# adau1772-1372-boosterpack.net
KiCad netlist of a schematic drawn in EAGLE
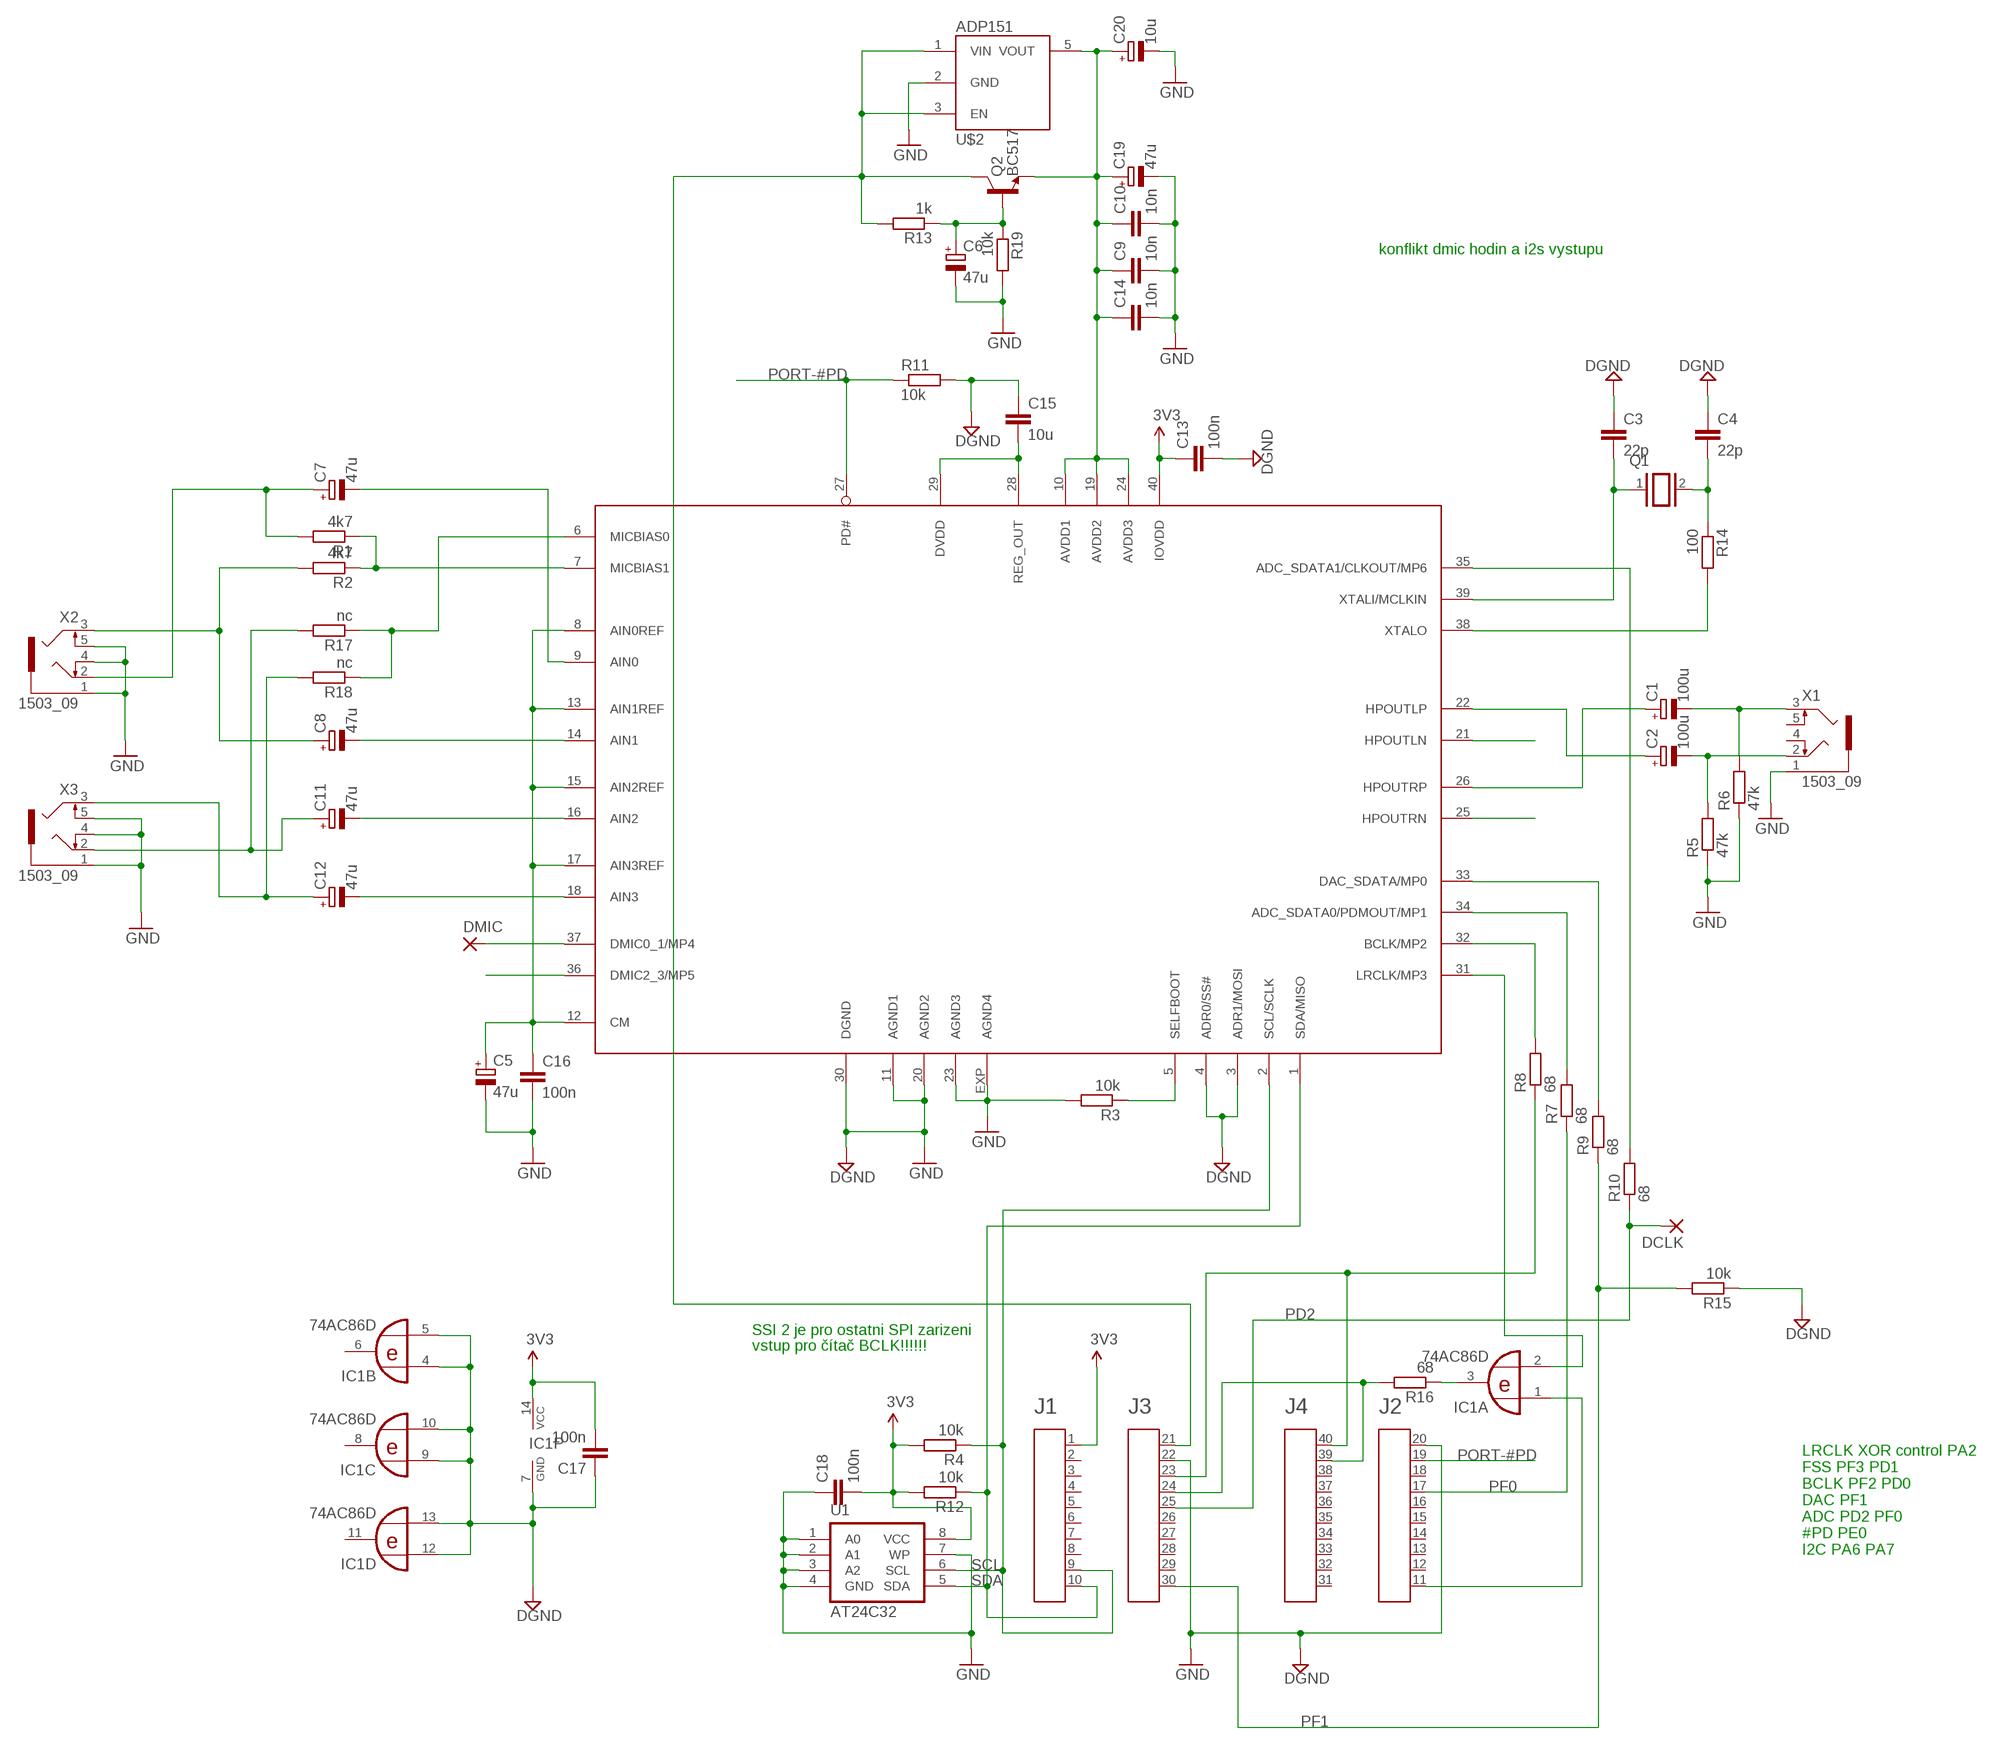
[diagram p0: schematic, sheet 1]

(export (version "E")
  (design (tool "Eeschema 10.0.6"))
  (components
    (comp (ref "A1")
      (value "HEADER4X10-BOOSTERPACK")
      (footprint "eagle-import:4X10-BOOSTERPACK")
      (libsource (lib "eagle-import") (part "HEADER4X10-BOOSTERPACK"))
    )
    (comp (ref "C1")
      (value "100u")
      (footprint "eagle-import:E2,5-7")
      (libsource (lib "eagle-import") (part "CPOL-EUE2.5-7"))
    )
    (comp (ref "C2")
      (value "100u")
      (footprint "eagle-import:E2,5-7")
      (libsource (lib "eagle-import") (part "CPOL-EUE2.5-7"))
    )
    (comp (ref "C3")
      (value "22p")
      (footprint "eagle-import:C0805K")
      (libsource (lib "eagle-import") (part "C-EUC0805K"))
    )
    (comp (ref "C4")
      (value "22p")
      (footprint "eagle-import:C0805K")
      (libsource (lib "eagle-import") (part "C-EUC0805K"))
    )
    (comp (ref "C5")
      (value "47u")
      (footprint "eagle-import:SMC_C")
      (libsource (lib "eagle-import") (part "CPOL-EUSMCC"))
    )
    (comp (ref "C6")
      (value "47u")
      (footprint "eagle-import:E2-5")
      (libsource (lib "eagle-import") (part "CPOL-EUE2-5"))
    )
    (comp (ref "C7")
      (value "47u")
      (footprint "eagle-import:E2-5")
      (libsource (lib "eagle-import") (part "CPOL-EUE2-5"))
    )
    (comp (ref "C8")
      (value "47u")
      (footprint "eagle-import:E2-5")
      (libsource (lib "eagle-import") (part "CPOL-EUE2-5"))
    )
    (comp (ref "C9")
      (value "10n")
      (footprint "eagle-import:C0805")
      (libsource (lib "eagle-import") (part "C-EUC0805"))
    )
    (comp (ref "C10")
      (value "10n")
      (footprint "eagle-import:C0805")
      (libsource (lib "eagle-import") (part "C-EUC0805"))
    )
    (comp (ref "C11")
      (value "47u")
      (footprint "eagle-import:E2-5")
      (libsource (lib "eagle-import") (part "CPOL-EUE2-5"))
    )
    (comp (ref "C12")
      (value "47u")
      (footprint "eagle-import:E2-5")
      (libsource (lib "eagle-import") (part "CPOL-EUE2-5"))
    )
    (comp (ref "C13")
      (value "100n")
      (footprint "eagle-import:C0805")
      (libsource (lib "eagle-import") (part "C-EUC0805"))
    )
    (comp (ref "C14")
      (value "10n")
      (footprint "eagle-import:C0805")
      (libsource (lib "eagle-import") (part "C-EUC0805"))
    )
    (comp (ref "C15")
      (value "10u")
      (footprint "eagle-import:C0805")
      (libsource (lib "eagle-import") (part "C-EUC0805"))
    )
    (comp (ref "C16")
      (value "100n")
      (footprint "eagle-import:C0805")
      (libsource (lib "eagle-import") (part "C-EUC0805"))
    )
    (comp (ref "C17")
      (value "100n")
      (footprint "eagle-import:C0805")
      (libsource (lib "eagle-import") (part "C-EUC0805"))
    )
    (comp (ref "C18")
      (value "100n")
      (footprint "eagle-import:C0805")
      (libsource (lib "eagle-import") (part "C-EUC0805"))
    )
    (comp (ref "C19")
      (value "47u")
      (footprint "eagle-import:E2-5")
      (libsource (lib "eagle-import") (part "CPOL-EUE2-5"))
    )
    (comp (ref "C20")
      (value "10u")
      (footprint "eagle-import:SMC_A")
      (libsource (lib "eagle-import") (part "CPOL-EUSMCA"))
    )
    (comp (ref "DCLK")
      (value "SMD2")
      (footprint "eagle-import:SMD1,27-2,54")
      (libsource (lib "eagle-import") (part "SMD2"))
    )
    (comp (ref "DMIC")
      (value "SMD2")
      (footprint "eagle-import:SMD1,27-2,54")
      (libsource (lib "eagle-import") (part "SMD2"))
    )
    (comp (ref "IC1")
      (value "74AC86D")
      (footprint "eagle-import:SO14")
      (libsource (lib "eagle-import") (part "7486DAC"))
    )
    (comp (ref "Q1")
      (value "XTAL/S")
      (footprint "eagle-import:QS")
      (libsource (lib "eagle-import") (part "XTAL/S"))
    )
    (comp (ref "Q2")
      (value "BC517")
      (footprint "eagle-import:TO92-")
      (libsource (lib "eagle-import") (part "BC550"))
    )
    (comp (ref "R1")
      (value "4k7")
      (footprint "eagle-import:R1206")
      (libsource (lib "eagle-import") (part "R-EU_R1206"))
    )
    (comp (ref "R2")
      (value "4k7")
      (footprint "eagle-import:R1206")
      (libsource (lib "eagle-import") (part "R-EU_R1206"))
    )
    (comp (ref "R3")
      (value "10k")
      (footprint "eagle-import:R1206")
      (libsource (lib "eagle-import") (part "R-EU_R1206"))
    )
    (comp (ref "R4")
      (value "10k")
      (footprint "eagle-import:R0805")
      (libsource (lib "eagle-import") (part "R-EU_R0805"))
    )
    (comp (ref "R5")
      (value "47k")
      (footprint "eagle-import:R0805")
      (libsource (lib "eagle-import") (part "R-EU_R0805"))
    )
    (comp (ref "R6")
      (value "47k")
      (footprint "eagle-import:R0805")
      (libsource (lib "eagle-import") (part "R-EU_R0805"))
    )
    (comp (ref "R7")
      (value "68")
      (footprint "eagle-import:R1206")
      (libsource (lib "eagle-import") (part "R-EU_R1206"))
    )
    (comp (ref "R8")
      (value "68")
      (footprint "eagle-import:R1206")
      (libsource (lib "eagle-import") (part "R-EU_R1206"))
    )
    (comp (ref "R9")
      (value "68")
      (footprint "eagle-import:R1206")
      (libsource (lib "eagle-import") (part "R-EU_R1206"))
    )
    (comp (ref "R10")
      (value "68")
      (footprint "eagle-import:R1206")
      (libsource (lib "eagle-import") (part "R-EU_R1206"))
    )
    (comp (ref "R11")
      (value "10k")
      (footprint "eagle-import:R0805")
      (libsource (lib "eagle-import") (part "R-EU_R0805"))
    )
    (comp (ref "R12")
      (value "10k")
      (footprint "eagle-import:R0805")
      (libsource (lib "eagle-import") (part "R-EU_R0805"))
    )
    (comp (ref "R13")
      (value "1k")
      (footprint "eagle-import:R0805")
      (libsource (lib "eagle-import") (part "R-EU_R0805"))
    )
    (comp (ref "R14")
      (value "100")
      (footprint "eagle-import:R0805")
      (libsource (lib "eagle-import") (part "R-EU_R0805"))
    )
    (comp (ref "R15")
      (value "10k")
      (footprint "eagle-import:R1206")
      (libsource (lib "eagle-import") (part "R-EU_R1206"))
    )
    (comp (ref "R16")
      (value "68")
      (footprint "eagle-import:R1206")
      (libsource (lib "eagle-import") (part "R-EU_R1206"))
    )
    (comp (ref "R17")
      (value "nc")
      (footprint "eagle-import:R1206")
      (libsource (lib "eagle-import") (part "R-EU_R1206"))
    )
    (comp (ref "R18")
      (value "nc")
      (footprint "eagle-import:R1206")
      (libsource (lib "eagle-import") (part "R-EU_R1206"))
    )
    (comp (ref "R19")
      (value "10k")
      (footprint "eagle-import:R0805")
      (libsource (lib "eagle-import") (part "R-EU_R0805"))
    )
    (comp (ref "U$1")
      (value "ADAU1772")
      (footprint "eagle-import:LFPSC-40")
      (libsource (lib "eagle-import") (part "ADAU1772"))
    )
    (comp (ref "U$2")
      (value "ADP151")
      (footprint "eagle-import:SOT23-5")
      (libsource (lib "eagle-import") (part "ADP151"))
    )
    (comp (ref "U1")
      (value "AT24C32")
      (footprint "eagle-import:SO08-8S1")
      (libsource (lib "eagle-import") (part "AT24CXX"))
    )
    (comp (ref "X1")
      (value "1503_09")
      (footprint "eagle-import:1503_09")
      (libsource (lib "eagle-import") (part "1503_09"))
    )
    (comp (ref "X2")
      (value "1503_09")
      (footprint "eagle-import:1503_09")
      (fields (field (name "OC_FARNELL") "1243244") (field (name "OC_NEWARK") "unknown"))
      (libsource (lib "eagle-import") (part "1503_09"))
    )
    (comp (ref "X3")
      (value "1503_09")
      (footprint "eagle-import:1503_09")
      (fields (field (name "OC_FARNELL") "1243244") (field (name "OC_NEWARK") "unknown"))
      (libsource (lib "eagle-import") (part "1503_09"))
    )
  )
  (nets
    (net (code "1") (name "/PD2") (class "Default")
      (node (ref "A1") (pin "25") (pinfunction "P$25_25") (pintype "bidirectional"))
      (node (ref "DCLK") (pin "1") (pinfunction "P_1") (pintype "passive"))
      (node (ref "R10") (pin "1") (pinfunction "1_1") (pintype "passive"))
    )
    (net (code "2") (name "/PF0") (class "Default")
      (node (ref "A1") (pin "17") (pinfunction "P$17_17") (pintype "bidirectional"))
      (node (ref "R7") (pin "1") (pinfunction "1_1") (pintype "passive"))
    )
    (net (code "3") (name "/PF1") (class "Default")
      (node (ref "A1") (pin "30") (pinfunction "P$30_30") (pintype "bidirectional"))
      (node (ref "R15") (pin "2") (pinfunction "2_2") (pintype "passive"))
      (node (ref "R9") (pin "1") (pinfunction "1_1") (pintype "passive"))
    )
    (net (code "4") (name "/PORT-#PD") (class "Default")
      (node (ref "A1") (pin "19") (pinfunction "P$19_19") (pintype "bidirectional"))
      (node (ref "R11") (pin "1") (pinfunction "1_1") (pintype "passive"))
      (node (ref "U$1") (pin "27") (pinfunction "PD#_27") (pintype "bidirectional"))
    )
    (net (code "5") (name "/SCL") (class "Default")
      (node (ref "A1") (pin "9") (pinfunction "P$9_9") (pintype "bidirectional"))
      (node (ref "R4") (pin "1") (pinfunction "1_1") (pintype "passive"))
      (node (ref "U$1") (pin "2") (pinfunction "SCL/SCLK_2") (pintype "bidirectional"))
      (node (ref "U1") (pin "6") (pinfunction "SCL_6") (pintype "bidirectional"))
    )
    (net (code "6") (name "/SDA") (class "Default")
      (node (ref "A1") (pin "10") (pinfunction "P$10_10") (pintype "bidirectional"))
      (node (ref "R12") (pin "1") (pinfunction "1_1") (pintype "passive"))
      (node (ref "U$1") (pin "1") (pinfunction "SDA/MISO_1") (pintype "bidirectional"))
      (node (ref "U1") (pin "5") (pinfunction "SDA_5") (pintype "bidirectional"))
    )
    (net (code "7") (name "3V3") (class "Default")
      (node (ref "A1") (pin "1") (pinfunction "P$1_1") (pintype "bidirectional"))
      (node (ref "C13") (pin "1") (pinfunction "1_1") (pintype "passive"))
      (node (ref "C17") (pin "2") (pinfunction "2_2") (pintype "passive"))
      (node (ref "C18") (pin "2") (pinfunction "2_2") (pintype "passive"))
      (node (ref "IC1") (pin "14") (pinfunction "VCC_14") (pintype "power_in"))
      (node (ref "R12") (pin "2") (pinfunction "2_2") (pintype "passive"))
      (node (ref "R4") (pin "2") (pinfunction "2_2") (pintype "passive"))
      (node (ref "U$1") (pin "40") (pinfunction "IOVDD_40") (pintype "bidirectional"))
      (node (ref "U1") (pin "8") (pinfunction "VCC_8") (pintype "power_in"))
    )
    (net (code "8") (name "DGND") (class "Default")
      (node (ref "A1") (pin "20") (pinfunction "P$20_20") (pintype "bidirectional"))
      (node (ref "A1") (pin "22") (pinfunction "P$22_22") (pintype "bidirectional"))
      (node (ref "C10") (pin "2") (pinfunction "2_2") (pintype "passive"))
      (node (ref "C13") (pin "2") (pinfunction "2_2") (pintype "passive"))
      (node (ref "C14") (pin "2") (pinfunction "2_2") (pintype "passive"))
      (node (ref "C15") (pin "1") (pinfunction "1_1") (pintype "passive"))
      (node (ref "C16") (pin "2") (pinfunction "2_2") (pintype "passive"))
      (node (ref "C17") (pin "1") (pinfunction "1_1") (pintype "passive"))
      (node (ref "C18") (pin "1") (pinfunction "1_1") (pintype "passive"))
      (node (ref "C19") (pin "-") (pinfunction "-_-") (pintype "passive"))
      (node (ref "C20") (pin "-") (pinfunction "-_-") (pintype "passive"))
      (node (ref "C3") (pin "1") (pinfunction "1_1") (pintype "passive"))
      (node (ref "C4") (pin "1") (pinfunction "1_1") (pintype "passive"))
      (node (ref "C5") (pin "-") (pinfunction "-_-") (pintype "passive"))
      (node (ref "C6") (pin "-") (pinfunction "-_-") (pintype "passive"))
      (node (ref "C9") (pin "2") (pinfunction "2_2") (pintype "passive"))
      (node (ref "IC1") (pin "10") (pinfunction "I1_10") (pintype "input"))
      (node (ref "IC1") (pin "12") (pinfunction "I0_12") (pintype "input"))
      (node (ref "IC1") (pin "13") (pinfunction "I1_13") (pintype "input"))
      (node (ref "IC1") (pin "4") (pinfunction "I0_4") (pintype "input"))
      (node (ref "IC1") (pin "5") (pinfunction "I1_5") (pintype "input"))
      (node (ref "IC1") (pin "7") (pinfunction "GND_7") (pintype "power_in"))
      (node (ref "IC1") (pin "9") (pinfunction "I0_9") (pintype "input"))
      (node (ref "R11") (pin "2") (pinfunction "2_2") (pintype "passive"))
      (node (ref "R15") (pin "1") (pinfunction "1_1") (pintype "passive"))
      (node (ref "R19") (pin "2") (pinfunction "2_2") (pintype "passive"))
      (node (ref "R3") (pin "2") (pinfunction "2_2") (pintype "passive"))
      (node (ref "R5") (pin "1") (pinfunction "1_1") (pintype "passive"))
      (node (ref "R6") (pin "1") (pinfunction "1_1") (pintype "passive"))
      (node (ref "U$1") (pin "11") (pinfunction "AGND1_11") (pintype "bidirectional"))
      (node (ref "U$1") (pin "20") (pinfunction "AGND2_20") (pintype "bidirectional"))
      (node (ref "U$1") (pin "23") (pinfunction "AGND3_23") (pintype "bidirectional"))
      (node (ref "U$1") (pin "3") (pinfunction "ADR1/MOSI_3") (pintype "bidirectional"))
      (node (ref "U$1") (pin "30") (pinfunction "DGND_30") (pintype "bidirectional"))
      (node (ref "U$1") (pin "4") (pinfunction "ADR0/SS#_4") (pintype "bidirectional"))
      (node (ref "U$1") (pin "EXP") (pinfunction "AGND4_EXP") (pintype "bidirectional"))
      (node (ref "U$2") (pin "2") (pinfunction "GND_2") (pintype "bidirectional"))
      (node (ref "U1") (pin "1") (pinfunction "A0_1") (pintype "input"))
      (node (ref "U1") (pin "2") (pinfunction "A1_2") (pintype "input"))
      (node (ref "U1") (pin "3") (pinfunction "A2_3") (pintype "input"))
      (node (ref "U1") (pin "4") (pinfunction "GND_4") (pintype "power_in"))
      (node (ref "U1") (pin "7") (pinfunction "WP_7") (pintype "bidirectional"))
      (node (ref "X1") (pin "1") (pinfunction "1_1") (pintype "passive"))
      (node (ref "X2") (pin "1") (pinfunction "1_1") (pintype "passive"))
      (node (ref "X2") (pin "4") (pinfunction "4_4") (pintype "passive"))
      (node (ref "X2") (pin "5") (pinfunction "5_5") (pintype "passive"))
      (node (ref "X3") (pin "1") (pinfunction "1_1") (pintype "passive"))
      (node (ref "X3") (pin "4") (pinfunction "4_4") (pintype "passive"))
      (node (ref "X3") (pin "5") (pinfunction "5_5") (pintype "passive"))
    )
    (net (code "9") (name "Net-(A1-P$11)") (class "Default")
      (node (ref "A1") (pin "11") (pinfunction "P$11_11") (pintype "bidirectional"))
      (node (ref "IC1") (pin "1") (pinfunction "I0_1") (pintype "input"))
    )
    (net (code "10") (name "Net-(A1-P$21)") (class "Default")
      (node (ref "A1") (pin "21") (pinfunction "P$21_21") (pintype "bidirectional"))
      (node (ref "Q2") (pin "3") (pinfunction "C_3") (pintype "passive"))
      (node (ref "R13") (pin "2") (pinfunction "2_2") (pintype "passive"))
      (node (ref "U$2") (pin "1") (pinfunction "VIN_1") (pintype "bidirectional"))
      (node (ref "U$2") (pin "3") (pinfunction "EN_3") (pintype "bidirectional"))
    )
    (net (code "11") (name "Net-(A1-P$23)") (class "Default")
      (node (ref "A1") (pin "23") (pinfunction "P$23_23") (pintype "bidirectional"))
      (node (ref "A1") (pin "40") (pinfunction "P$40_40") (pintype "bidirectional"))
      (node (ref "R8") (pin "1") (pinfunction "1_1") (pintype "passive"))
    )
    (net (code "12") (name "Net-(A1-P$24)") (class "Default")
      (node (ref "A1") (pin "24") (pinfunction "P$24_24") (pintype "bidirectional"))
      (node (ref "A1") (pin "39") (pinfunction "P$39_39") (pintype "bidirectional"))
      (node (ref "R16") (pin "2") (pinfunction "2_2") (pintype "passive"))
    )
    (net (code "13") (name "Net-(C1-Pad-)") (class "Default")
      (node (ref "C1") (pin "-") (pinfunction "-_-") (pintype "passive"))
      (node (ref "R6") (pin "2") (pinfunction "2_2") (pintype "passive"))
      (node (ref "X1") (pin "3") (pinfunction "3_3") (pintype "passive"))
    )
    (net (code "14") (name "Net-(C2-Pad-)") (class "Default")
      (node (ref "C2") (pin "-") (pinfunction "-_-") (pintype "passive"))
      (node (ref "R5") (pin "2") (pinfunction "2_2") (pintype "passive"))
      (node (ref "X1") (pin "2") (pinfunction "2_2") (pintype "passive"))
    )
    (net (code "15") (name "Net-(C4-Pad2)") (class "Default")
      (node (ref "C4") (pin "2") (pinfunction "2_2") (pintype "passive"))
      (node (ref "Q1") (pin "2") (pinfunction "2_2") (pintype "passive"))
      (node (ref "R14") (pin "1") (pinfunction "1_1") (pintype "passive"))
    )
    (net (code "16") (name "Net-(C7-Pad+)") (class "Default")
      (node (ref "C7") (pin "+") (pinfunction "+_+") (pintype "passive"))
      (node (ref "R1") (pin "2") (pinfunction "2_2") (pintype "passive"))
      (node (ref "X2") (pin "2") (pinfunction "2_2") (pintype "passive"))
    )
    (net (code "17") (name "Net-(C8-Pad+)") (class "Default")
      (node (ref "C8") (pin "+") (pinfunction "+_+") (pintype "passive"))
      (node (ref "R2") (pin "2") (pinfunction "2_2") (pintype "passive"))
      (node (ref "X2") (pin "3") (pinfunction "3_3") (pintype "passive"))
    )
    (net (code "18") (name "Net-(C11-Pad+)") (class "Default")
      (node (ref "C11") (pin "+") (pinfunction "+_+") (pintype "passive"))
      (node (ref "R17") (pin "2") (pinfunction "2_2") (pintype "passive"))
      (node (ref "X3") (pin "2") (pinfunction "2_2") (pintype "passive"))
    )
    (net (code "19") (name "Net-(C12-Pad+)") (class "Default")
      (node (ref "C12") (pin "+") (pinfunction "+_+") (pintype "passive"))
      (node (ref "R18") (pin "2") (pinfunction "2_2") (pintype "passive"))
      (node (ref "X3") (pin "3") (pinfunction "3_3") (pintype "passive"))
    )
    (net (code "20") (name "Net-(DMIC-P)") (class "Default")
      (node (ref "DMIC") (pin "1") (pinfunction "P_1") (pintype "passive"))
      (node (ref "U$1") (pin "37") (pinfunction "DMIC0_1/MP4_37") (pintype "bidirectional"))
    )
    (net (code "21") (name "Net-(IC1A-I1)") (class "Default")
      (node (ref "IC1") (pin "2") (pinfunction "I1_2") (pintype "input"))
      (node (ref "U$1") (pin "31") (pinfunction "LRCLK/MP3_31") (pintype "bidirectional"))
    )
    (net (code "22") (name "Net-(IC1A-O)") (class "Default")
      (node (ref "IC1") (pin "3") (pinfunction "O_3") (pintype "output"))
      (node (ref "R16") (pin "1") (pinfunction "1_1") (pintype "passive"))
    )
    (net (code "23") (name "Net-(Q2-B)") (class "Default")
      (node (ref "C6") (pin "+") (pinfunction "+_+") (pintype "passive"))
      (node (ref "Q2") (pin "2") (pinfunction "B_2") (pintype "passive"))
      (node (ref "R13") (pin "1") (pinfunction "1_1") (pintype "passive"))
      (node (ref "R19") (pin "1") (pinfunction "1_1") (pintype "passive"))
    )
    (net (code "24") (name "Net-(Q2-E)") (class "Default")
      (node (ref "C10") (pin "1") (pinfunction "1_1") (pintype "passive"))
      (node (ref "C14") (pin "1") (pinfunction "1_1") (pintype "passive"))
      (node (ref "C19") (pin "+") (pinfunction "+_+") (pintype "passive"))
      (node (ref "C20") (pin "+") (pinfunction "+_+") (pintype "passive"))
      (node (ref "C9") (pin "1") (pinfunction "1_1") (pintype "passive"))
      (node (ref "Q2") (pin "1") (pinfunction "E_1") (pintype "passive"))
      (node (ref "U$1") (pin "10") (pinfunction "AVDD1_10") (pintype "bidirectional"))
      (node (ref "U$1") (pin "19") (pinfunction "AVDD2_19") (pintype "bidirectional"))
      (node (ref "U$1") (pin "24") (pinfunction "AVDD3_24") (pintype "bidirectional"))
      (node (ref "U$2") (pin "5") (pinfunction "VOUT_5") (pintype "bidirectional"))
    )
    (net (code "25") (name "Net-(U$1-ADC_SDATA0{slash}PDMOUT{slash}MP1)") (class "Default")
      (node (ref "R7") (pin "2") (pinfunction "2_2") (pintype "passive"))
      (node (ref "U$1") (pin "34") (pinfunction "ADC_SDATA0/PDMOUT/MP1_34") (pintype "bidirectional"))
    )
    (net (code "26") (name "Net-(U$1-ADC_SDATA1{slash}CLKOUT{slash}MP6)") (class "Default")
      (node (ref "R10") (pin "2") (pinfunction "2_2") (pintype "passive"))
      (node (ref "U$1") (pin "35") (pinfunction "ADC_SDATA1/CLKOUT/MP6_35") (pintype "bidirectional"))
    )
    (net (code "27") (name "Net-(U$1-AIN0)") (class "Default")
      (node (ref "C7") (pin "-") (pinfunction "-_-") (pintype "passive"))
      (node (ref "U$1") (pin "9") (pinfunction "AIN0_9") (pintype "bidirectional"))
    )
    (net (code "28") (name "Net-(U$1-AIN0REF)") (class "Default")
      (node (ref "C16") (pin "1") (pinfunction "1_1") (pintype "passive"))
      (node (ref "C5") (pin "+") (pinfunction "+_+") (pintype "passive"))
      (node (ref "U$1") (pin "12") (pinfunction "CM_12") (pintype "bidirectional"))
      (node (ref "U$1") (pin "13") (pinfunction "AIN1REF_13") (pintype "bidirectional"))
      (node (ref "U$1") (pin "15") (pinfunction "AIN2REF_15") (pintype "bidirectional"))
      (node (ref "U$1") (pin "17") (pinfunction "AIN3REF_17") (pintype "bidirectional"))
      (node (ref "U$1") (pin "8") (pinfunction "AIN0REF_8") (pintype "bidirectional"))
    )
    (net (code "29") (name "Net-(U$1-AIN1)") (class "Default")
      (node (ref "C8") (pin "-") (pinfunction "-_-") (pintype "passive"))
      (node (ref "U$1") (pin "14") (pinfunction "AIN1_14") (pintype "bidirectional"))
    )
    (net (code "30") (name "Net-(U$1-AIN2)") (class "Default")
      (node (ref "C11") (pin "-") (pinfunction "-_-") (pintype "passive"))
      (node (ref "U$1") (pin "16") (pinfunction "AIN2_16") (pintype "bidirectional"))
    )
    (net (code "31") (name "Net-(U$1-AIN3)") (class "Default")
      (node (ref "C12") (pin "-") (pinfunction "-_-") (pintype "passive"))
      (node (ref "U$1") (pin "18") (pinfunction "AIN3_18") (pintype "bidirectional"))
    )
    (net (code "32") (name "Net-(U$1-BCLK{slash}MP2)") (class "Default")
      (node (ref "R8") (pin "2") (pinfunction "2_2") (pintype "passive"))
      (node (ref "U$1") (pin "32") (pinfunction "BCLK/MP2_32") (pintype "bidirectional"))
    )
    (net (code "33") (name "Net-(U$1-DAC_SDATA{slash}MP0)") (class "Default")
      (node (ref "R9") (pin "2") (pinfunction "2_2") (pintype "passive"))
      (node (ref "U$1") (pin "33") (pinfunction "DAC_SDATA/MP0_33") (pintype "bidirectional"))
    )
    (net (code "34") (name "Net-(U$1-DVDD)") (class "Default")
      (node (ref "C15") (pin "2") (pinfunction "2_2") (pintype "passive"))
      (node (ref "U$1") (pin "28") (pinfunction "REG_OUT_28") (pintype "bidirectional"))
      (node (ref "U$1") (pin "29") (pinfunction "DVDD_29") (pintype "bidirectional"))
    )
    (net (code "35") (name "Net-(U$1-HPOUTLP)") (class "Default")
      (node (ref "C2") (pin "+") (pinfunction "+_+") (pintype "passive"))
      (node (ref "U$1") (pin "22") (pinfunction "HPOUTLP_22") (pintype "bidirectional"))
    )
    (net (code "36") (name "Net-(U$1-HPOUTRP)") (class "Default")
      (node (ref "C1") (pin "+") (pinfunction "+_+") (pintype "passive"))
      (node (ref "U$1") (pin "26") (pinfunction "HPOUTRP_26") (pintype "bidirectional"))
    )
    (net (code "37") (name "Net-(U$1-MICBIAS0)") (class "Default")
      (node (ref "R17") (pin "1") (pinfunction "1_1") (pintype "passive"))
      (node (ref "R18") (pin "1") (pinfunction "1_1") (pintype "passive"))
      (node (ref "U$1") (pin "6") (pinfunction "MICBIAS0_6") (pintype "bidirectional"))
    )
    (net (code "38") (name "Net-(U$1-MICBIAS1)") (class "Default")
      (node (ref "R1") (pin "1") (pinfunction "1_1") (pintype "passive"))
      (node (ref "R2") (pin "1") (pinfunction "1_1") (pintype "passive"))
      (node (ref "U$1") (pin "7") (pinfunction "MICBIAS1_7") (pintype "bidirectional"))
    )
    (net (code "39") (name "Net-(U$1-SELFBOOT)") (class "Default")
      (node (ref "R3") (pin "1") (pinfunction "1_1") (pintype "passive"))
      (node (ref "U$1") (pin "5") (pinfunction "SELFBOOT_5") (pintype "bidirectional"))
    )
    (net (code "40") (name "Net-(U$1-XTALI{slash}MCLKIN)") (class "Default")
      (node (ref "C3") (pin "2") (pinfunction "2_2") (pintype "passive"))
      (node (ref "Q1") (pin "1") (pinfunction "1_1") (pintype "passive"))
      (node (ref "U$1") (pin "39") (pinfunction "XTALI/MCLKIN_39") (pintype "bidirectional"))
    )
    (net (code "41") (name "Net-(U$1-XTALO)") (class "Default")
      (node (ref "R14") (pin "2") (pinfunction "2_2") (pintype "passive"))
      (node (ref "U$1") (pin "38") (pinfunction "XTALO_38") (pintype "bidirectional"))
    )
    (net (code "42") (name "unconnected-(A1-P$2-Pad2)") (class "Default")
      (node (ref "A1") (pin "2") (pinfunction "P$2_2") (pintype "bidirectional"))
    )
    (net (code "43") (name "unconnected-(A1-P$3-Pad3)") (class "Default")
      (node (ref "A1") (pin "3") (pinfunction "P$3_3") (pintype "bidirectional"))
    )
    (net (code "44") (name "unconnected-(A1-P$4-Pad4)") (class "Default")
      (node (ref "A1") (pin "4") (pinfunction "P$4_4") (pintype "bidirectional"))
    )
    (net (code "45") (name "unconnected-(A1-P$5-Pad5)") (class "Default")
      (node (ref "A1") (pin "5") (pinfunction "P$5_5") (pintype "bidirectional"))
    )
    (net (code "46") (name "unconnected-(A1-P$6-Pad6)") (class "Default")
      (node (ref "A1") (pin "6") (pinfunction "P$6_6") (pintype "bidirectional"))
    )
    (net (code "47") (name "unconnected-(A1-P$7-Pad7)") (class "Default")
      (node (ref "A1") (pin "7") (pinfunction "P$7_7") (pintype "bidirectional"))
    )
    (net (code "48") (name "unconnected-(A1-P$8-Pad8)") (class "Default")
      (node (ref "A1") (pin "8") (pinfunction "P$8_8") (pintype "bidirectional"))
    )
    (net (code "49") (name "unconnected-(A1-P$12-Pad12)") (class "Default")
      (node (ref "A1") (pin "12") (pinfunction "P$12_12") (pintype "bidirectional"))
    )
    (net (code "50") (name "unconnected-(A1-P$13-Pad13)") (class "Default")
      (node (ref "A1") (pin "13") (pinfunction "P$13_13") (pintype "bidirectional"))
    )
    (net (code "51") (name "unconnected-(A1-P$14-Pad14)") (class "Default")
      (node (ref "A1") (pin "14") (pinfunction "P$14_14") (pintype "bidirectional"))
    )
    (net (code "52") (name "unconnected-(A1-P$15-Pad15)") (class "Default")
      (node (ref "A1") (pin "15") (pinfunction "P$15_15") (pintype "bidirectional"))
    )
    (net (code "53") (name "unconnected-(A1-P$16-Pad16)") (class "Default")
      (node (ref "A1") (pin "16") (pinfunction "P$16_16") (pintype "bidirectional"))
    )
    (net (code "54") (name "unconnected-(A1-P$18-Pad18)") (class "Default")
      (node (ref "A1") (pin "18") (pinfunction "P$18_18") (pintype "bidirectional"))
    )
    (net (code "55") (name "unconnected-(A1-P$26-Pad26)") (class "Default")
      (node (ref "A1") (pin "26") (pinfunction "P$26_26") (pintype "bidirectional"))
    )
    (net (code "56") (name "unconnected-(A1-P$27-Pad27)") (class "Default")
      (node (ref "A1") (pin "27") (pinfunction "P$27_27") (pintype "bidirectional"))
    )
    (net (code "57") (name "unconnected-(A1-P$28-Pad28)") (class "Default")
      (node (ref "A1") (pin "28") (pinfunction "P$28_28") (pintype "bidirectional"))
    )
    (net (code "58") (name "unconnected-(A1-P$29-Pad29)") (class "Default")
      (node (ref "A1") (pin "29") (pinfunction "P$29_29") (pintype "bidirectional"))
    )
    (net (code "59") (name "unconnected-(A1-P$31-Pad31)") (class "Default")
      (node (ref "A1") (pin "31") (pinfunction "P$31_31") (pintype "bidirectional"))
    )
    (net (code "60") (name "unconnected-(A1-P$32-Pad32)") (class "Default")
      (node (ref "A1") (pin "32") (pinfunction "P$32_32") (pintype "bidirectional"))
    )
    (net (code "61") (name "unconnected-(A1-P$33-Pad33)") (class "Default")
      (node (ref "A1") (pin "33") (pinfunction "P$33_33") (pintype "bidirectional"))
    )
    (net (code "62") (name "unconnected-(A1-P$34-Pad34)") (class "Default")
      (node (ref "A1") (pin "34") (pinfunction "P$34_34") (pintype "bidirectional"))
    )
    (net (code "63") (name "unconnected-(A1-P$35-Pad35)") (class "Default")
      (node (ref "A1") (pin "35") (pinfunction "P$35_35") (pintype "bidirectional"))
    )
    (net (code "64") (name "unconnected-(A1-P$36-Pad36)") (class "Default")
      (node (ref "A1") (pin "36") (pinfunction "P$36_36") (pintype "bidirectional"))
    )
    (net (code "65") (name "unconnected-(A1-P$37-Pad37)") (class "Default")
      (node (ref "A1") (pin "37") (pinfunction "P$37_37") (pintype "bidirectional"))
    )
    (net (code "66") (name "unconnected-(A1-P$38-Pad38)") (class "Default")
      (node (ref "A1") (pin "38") (pinfunction "P$38_38") (pintype "bidirectional"))
    )
    (net (code "67") (name "unconnected-(IC1B-O-Pad6)") (class "Default")
      (node (ref "IC1") (pin "6") (pinfunction "O_6") (pintype "output"))
    )
    (net (code "68") (name "unconnected-(IC1C-O-Pad8)") (class "Default")
      (node (ref "IC1") (pin "8") (pinfunction "O_8") (pintype "output"))
    )
    (net (code "69") (name "unconnected-(IC1D-O-Pad11)") (class "Default")
      (node (ref "IC1") (pin "11") (pinfunction "O_11") (pintype "output"))
    )
    (net (code "70") (name "unconnected-(U$1-DMIC2_3{slash}MP5-Pad36)") (class "Default")
      (node (ref "U$1") (pin "36") (pinfunction "DMIC2_3/MP5_36") (pintype "bidirectional"))
    )
    (net (code "71") (name "unconnected-(U$1-HPOUTLN-Pad21)") (class "Default")
      (node (ref "U$1") (pin "21") (pinfunction "HPOUTLN_21") (pintype "bidirectional"))
    )
    (net (code "72") (name "unconnected-(U$1-HPOUTRN-Pad25)") (class "Default")
      (node (ref "U$1") (pin "25") (pinfunction "HPOUTRN_25") (pintype "bidirectional"))
    )
    (net (code "73") (name "unconnected-(X1-Pad4)") (class "Default")
      (node (ref "X1") (pin "4") (pinfunction "4_4") (pintype "passive"))
    )
    (net (code "74") (name "unconnected-(X1-Pad5)") (class "Default")
      (node (ref "X1") (pin "5") (pinfunction "5_5") (pintype "passive"))
    )
  )
)
